# BV100011_EERAM.net
KiCad netlist of a schematic drawn in Altium Designer
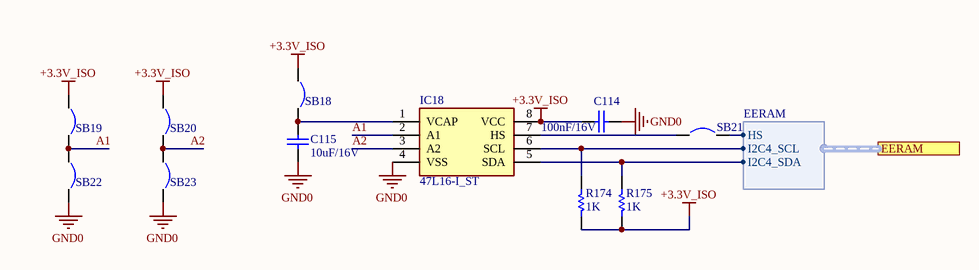
[diagram p0: BV100011_EERAM.SchDoc]

(export (version "E")
  (design (tool "Eeschema 10.0.6"))
  (components
    (comp (ref "C114")
      (value "100nF/16V")
      (footprint "C1210")
      (description "Capacitor (Semiconductor SIM Model)")
      (fields (field (name "PUBLISHER") "Altium Limited"))
      (libsource (lib "Miscellaneous Devices") (part "Cap Semi"))
    )
    (comp (ref "C115")
      (value "10uF/16V")
      (footprint "C1210")
      (description "Capacitor (Semiconductor SIM Model)")
      (fields (field (name "PUBLISHER") "Altium Limited"))
      (libsource (lib "Miscellaneous Devices") (part "Cap Semi"))
    )
    (comp (ref "IC18")
      (value "47L16-I_ST")
      (footprint "SamacSys:SOP65P640X120-8N")
      (description "Integrated Circuit")
      (fields
        (field (name "MANUFACTURER_PART_NUMBER") "47L16-I/ST")
        (field (name "MOUSER PART NUMBER") "579-47L16-I/ST")
      )
      (libsource (lib "*") (part "47L16-I_ST"))
    )
    (comp (ref "R174")
      (value "1K")
      (footprint "0402R")
      (description "Resistor")
      (fields (field (name "PUBLISHER") "Altium Limited"))
      (libsource (lib "Miscellaneous Devices") (part "Res1"))
    )
    (comp (ref "R175")
      (value "1K")
      (footprint "0402R")
      (description "Resistor")
      (fields (field (name "PUBLISHER") "Altium Limited"))
      (libsource (lib "Miscellaneous Devices") (part "Res1"))
    )
    (comp (ref "SB18")
      (value "Circuit Breaker")
      (footprint "SB_0603")
      (fields (field (name "PUBLISHER") "Altium Limited"))
      (libsource (lib "BV100011_UniversalSlave") (part "Circuit Breaker"))
    )
    (comp (ref "SB19")
      (value "Circuit Breaker")
      (footprint "SB_0603")
      (fields (field (name "PUBLISHER") "Altium Limited"))
      (libsource (lib "BV100011_UniversalSlave") (part "Circuit Breaker"))
    )
    (comp (ref "SB20")
      (value "Circuit Breaker")
      (footprint "SB_0603")
      (fields (field (name "PUBLISHER") "Altium Limited"))
      (libsource (lib "BV100011_UniversalSlave") (part "Circuit Breaker"))
    )
    (comp (ref "SB21")
      (value "Circuit Breaker")
      (footprint "SB_0603")
      (fields (field (name "PUBLISHER") "Altium Limited"))
      (libsource (lib "BV100011_UniversalSlave") (part "Circuit Breaker"))
    )
    (comp (ref "SB22")
      (value "Circuit Breaker")
      (footprint "SB_0603")
      (fields (field (name "PUBLISHER") "Altium Limited"))
      (libsource (lib "BV100011_UniversalSlave") (part "Circuit Breaker"))
    )
    (comp (ref "SB23")
      (value "Circuit Breaker")
      (footprint "SB_0603")
      (fields (field (name "PUBLISHER") "Altium Limited"))
      (libsource (lib "BV100011_UniversalSlave") (part "Circuit Breaker"))
    )
  )
  (nets
    (net (code "2") (name "+3.3V_ISO") (class "Default")
      (node (ref "C114") (pin "2") (pinfunction "2_2") (pintype "passive"))
      (node (ref "IC18") (pin "8") (pinfunction "VCC_8") (pintype "passive"))
      (node (ref "R174") (pin "1") (pinfunction "1_1") (pintype "passive"))
      (node (ref "R175") (pin "1") (pinfunction "1_1") (pintype "passive"))
      (node (ref "SB18") (pin "1") (pinfunction "1_1") (pintype "passive"))
      (node (ref "SB19") (pin "1") (pinfunction "1_1") (pintype "passive"))
      (node (ref "SB20") (pin "1") (pinfunction "1_1") (pintype "passive"))
    )
    (net (code "3") (name "/A1") (class "Default")
      (node (ref "IC18") (pin "2") (pinfunction "A1_2") (pintype "passive"))
      (node (ref "SB19") (pin "2") (pinfunction "2_2") (pintype "passive"))
      (node (ref "SB22") (pin "1") (pinfunction "1_1") (pintype "passive"))
    )
    (net (code "4") (name "/A2") (class "Default")
      (node (ref "IC18") (pin "3") (pinfunction "A2_3") (pintype "passive"))
      (node (ref "SB20") (pin "2") (pinfunction "2_2") (pintype "passive"))
      (node (ref "SB23") (pin "1") (pinfunction "1_1") (pintype "passive"))
    )
    (net (code "5") (name "/HS") (class "Default")
      (node (ref "SB21") (pin "2") (pinfunction "2_2") (pintype "passive"))
    )
    (net (code "6") (name "/I2C4_SCL") (class "Default")
      (node (ref "IC18") (pin "6") (pinfunction "SCL_6") (pintype "passive"))
      (node (ref "R174") (pin "2") (pinfunction "2_2") (pintype "passive"))
    )
    (net (code "7") (name "/I2C4_SDA") (class "Default")
      (node (ref "IC18") (pin "5") (pinfunction "SDA_5") (pintype "passive"))
      (node (ref "R175") (pin "2") (pinfunction "2_2") (pintype "passive"))
    )
    (net (code "9") (name "GND0") (class "Default")
      (node (ref "C114") (pin "1") (pinfunction "1_1") (pintype "passive"))
      (node (ref "C115") (pin "1") (pinfunction "1_1") (pintype "passive"))
      (node (ref "IC18") (pin "4") (pinfunction "VSS_4") (pintype "passive"))
      (node (ref "SB22") (pin "2") (pinfunction "2_2") (pintype "passive"))
      (node (ref "SB23") (pin "2") (pinfunction "2_2") (pintype "passive"))
    )
    (net (code "10") (name "Net-(IC18-HS)") (class "Default")
      (node (ref "IC18") (pin "7") (pinfunction "HS_7") (pintype "passive"))
      (node (ref "SB21") (pin "1") (pinfunction "1_1") (pintype "passive"))
    )
    (net (code "11") (name "Net-(IC18-VCAP)") (class "Default")
      (node (ref "C115") (pin "2") (pinfunction "2_2") (pintype "passive"))
      (node (ref "IC18") (pin "1") (pinfunction "VCAP_1") (pintype "passive"))
      (node (ref "SB18") (pin "2") (pinfunction "2_2") (pintype "passive"))
    )
  )
)
